# pca10156_sheet7_connectors.net
KiCad netlist of a schematic drawn in Altium Designer
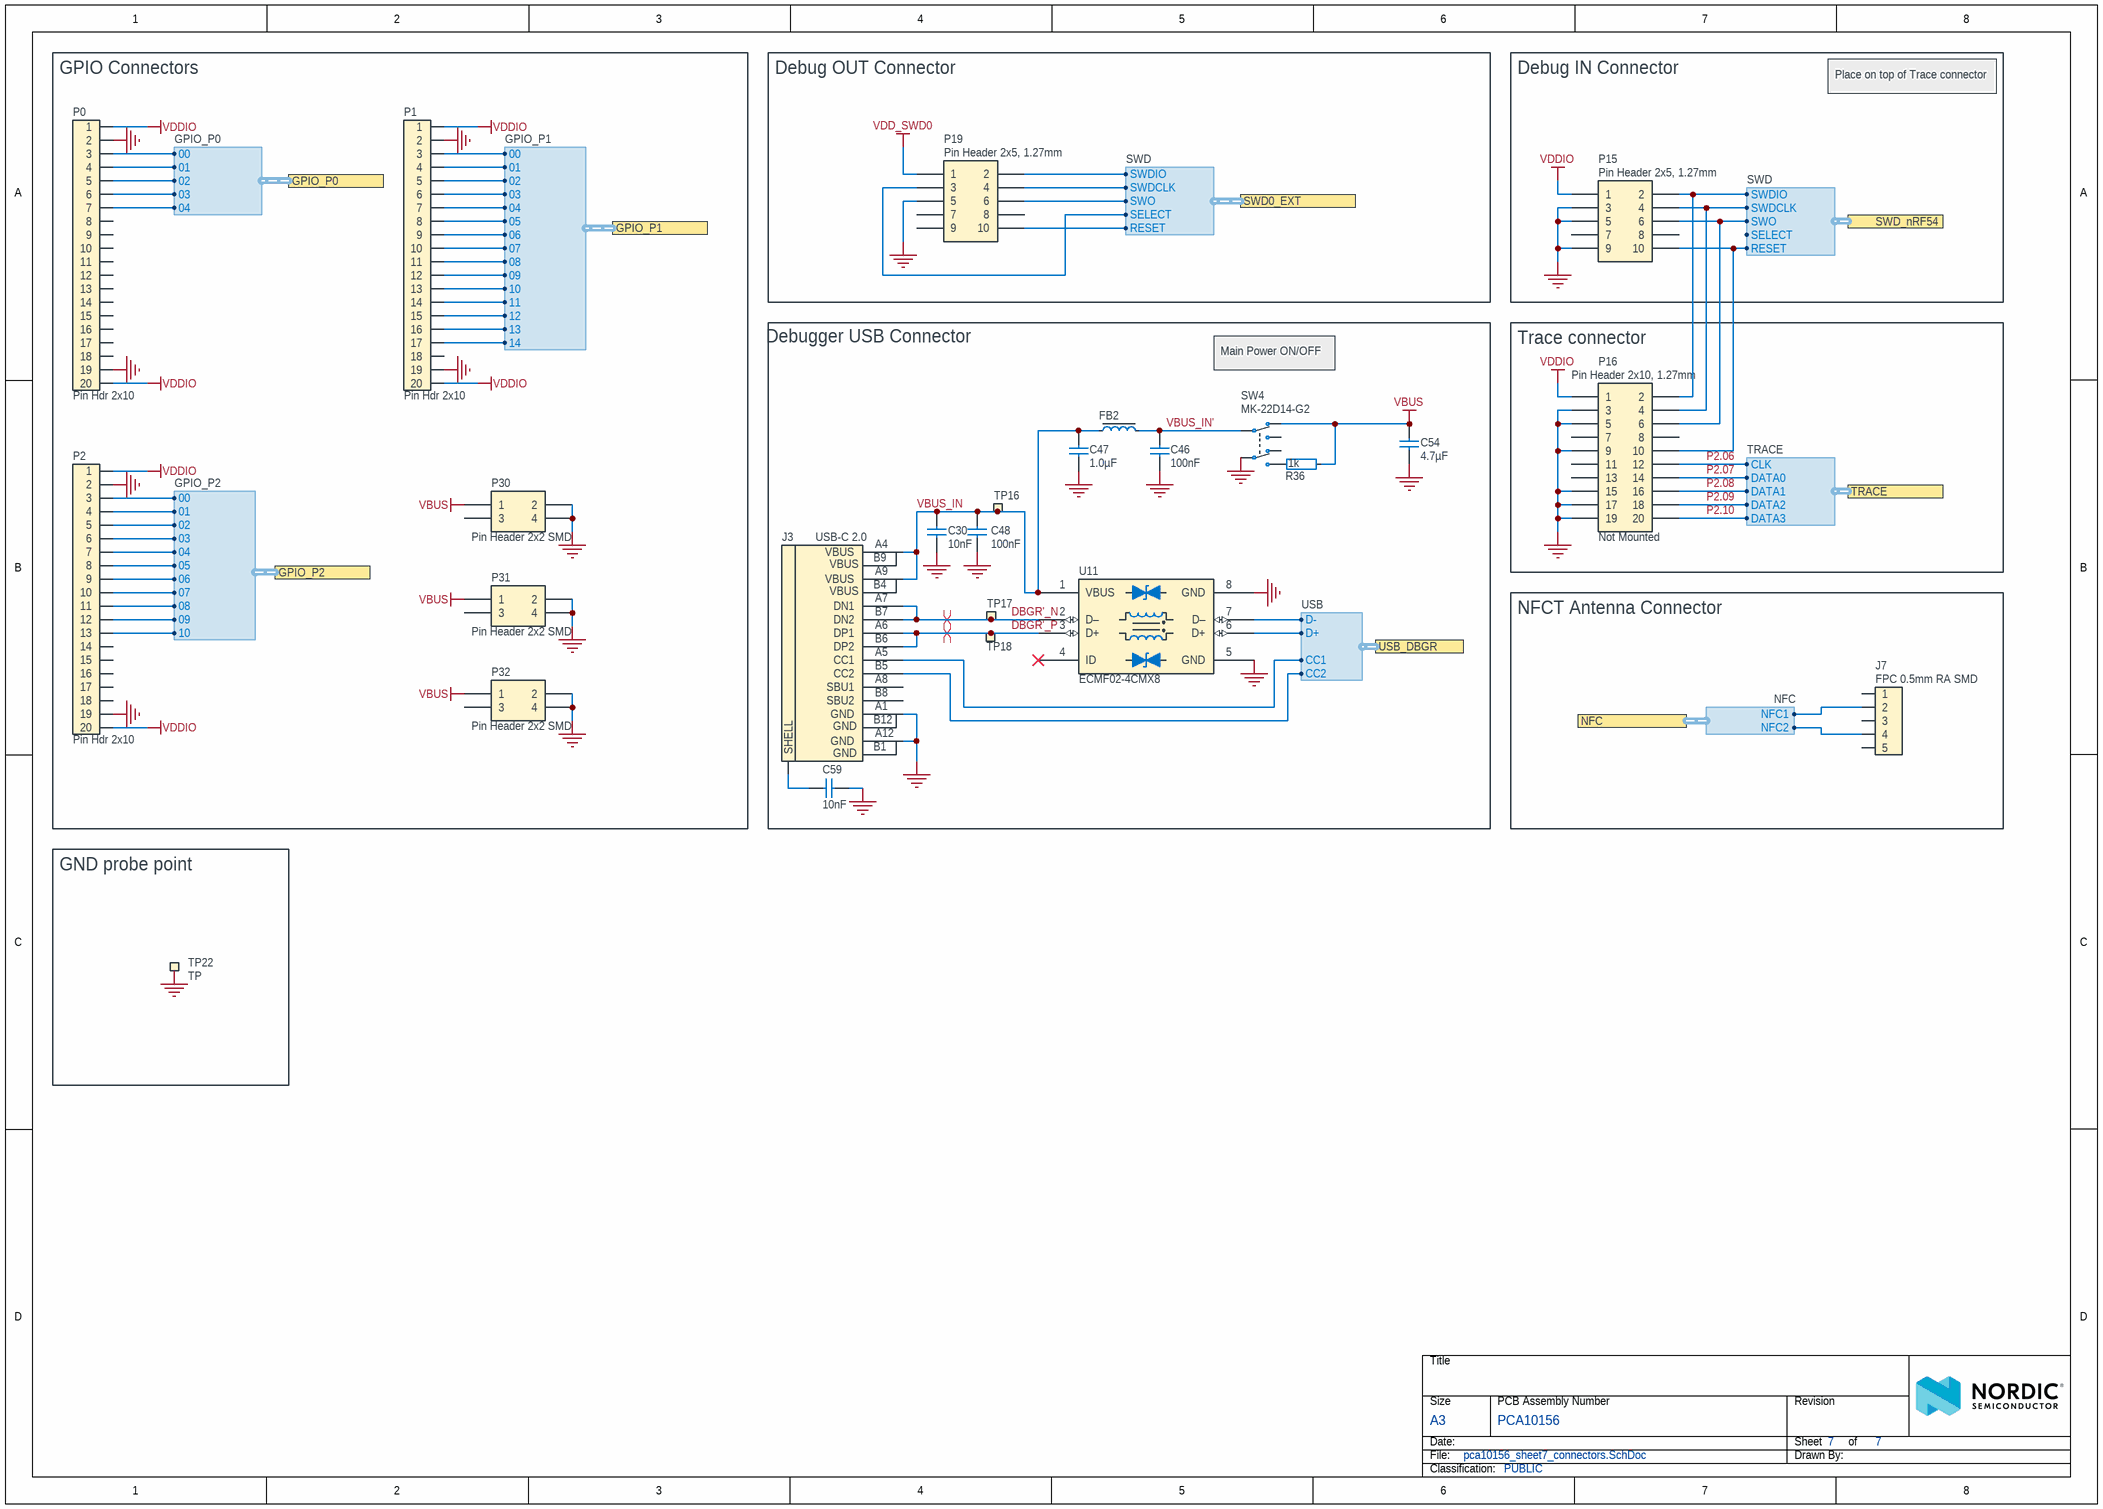
[diagram p0: pca10156_sheet7_connectors.SchDoc]

(export (version "E")
  (design (tool "Eeschema 10.0.6"))
  (components
    (comp (ref "C30")
      (value "10nF")
      (footprint "CAPC0603X03L_C")
      (description "Capacitor, X7R, ±10%")
      (fields
        (field (name "PART NUMBER") "C0201-10n")
        (field (name "MANUFACTURER") "N.A.")
        (field (name "AUTHOR") "rsk")
      )
      (libsource (lib "AltiumLib") (part "CAP"))
    )
    (comp (ref "C46")
      (value "100nF")
      (footprint "CAPC0603X03L_C")
      (description "Capacitor, X5R, ±10%")
      (fields
        (field (name "PART NUMBER") "C0201-100n")
        (field (name "MANUFACTURER") "N.A.")
        (field (name "AUTHOR") "rsk")
      )
      (libsource (lib "AltiumLib") (part "CAP"))
    )
    (comp (ref "C47")
      (value "1.0µF")
      (footprint "CAPC1005X04L")
      (description "Capacitor, Ceramic, X5R, ±10%, 16V")
      (fields
        (field (name "PART NUMBER") "C0402-1µ0-16V-X5R")
        (field (name "MANUFACTURER") "Murata")
        (field (name "AUTHOR") "rsk")
      )
      (libsource (lib "AltiumLib") (part "CAP"))
    )
    (comp (ref "C48")
      (value "100nF")
      (footprint "CAPC0603X03L_C")
      (description "Capacitor, X5R, ±10%")
      (fields
        (field (name "PART NUMBER") "C0201-100n")
        (field (name "MANUFACTURER") "N.A.")
        (field (name "AUTHOR") "rsk")
      )
      (libsource (lib "AltiumLib") (part "CAP"))
    )
    (comp (ref "C54")
      (value "4.7µF")
      (footprint "CAPC1608X06L")
      (description "Capacitor, X7S, ±10%, 10V")
      (fields
        (field (name "PART NUMBER") "C0603-4µ7-10V-X7S")
        (field (name "MANUFACTURER") "N.A.")
        (field (name "AUTHOR") "rsk")
      )
      (libsource (lib "AltiumLib") (part "CAP"))
    )
    (comp (ref "C59")
      (value "10nF")
      (footprint "CAPC1608X06L")
      (description "Capacitor, X7R, ±10%, 100V")
      (fields
        (field (name "PART NUMBER") "C0603-10n-100V-X7R")
        (field (name "MANUFACTURER") "Murata")
        (field (name "AUTHOR") "rsk")
      )
      (libsource (lib "") (part "CAP_1"))
    )
    (comp (ref "FB2")
      (value "120R/0.55A")
      (footprint "INDC1005X04L")
      (description "Ferrite Bead, 120 Ohm @ 100MHz, 500mA, 250 mOhm Max")
      (fields
        (field (name "PART NUMBER") "FB0402-120R@100M-500mA")
        (field (name "MANUFACTURER") "Murata")
        (field (name "AUTHOR") "rsk")
      )
      (libsource (lib "AltiumLib") (part "IND_F"))
    )
    (comp (ref "J3")
      (value "USB-C 2.0")
      (footprint "SD-80259-001")
      (description "USB-C Receptacle, 16 Pin, USB 2.0")
      (fields
        (field (name "PART NUMBER") "SD-80259-1021")
        (field (name "MANUFACTURER") "Bellweather Electronic Corp.")
        (field (name "AUTHOR") "getr")
      )
      (libsource (lib "AltiumLib") (part "USB4110"))
    )
    (comp (ref "J7")
      (value "FPC 0.5mm RA SMD")
      (footprint "FPC_05P-0.5mm-RA-SMD")
      (description "0.5mm FPC, 5P,Right Angle SMT,Double Contact,H=1.2mm,White, Tin plated")
      (fields
        (field (name "PART NUMBER") "FPC_05P-0.5mm-RA-SMD")
        (field (name "MANUFACTURER") "WCON")
        (field (name "AUTHOR") "rsk")
      )
      (libsource (lib "AltiumLib") (part "CONN-5"))
    )
    (comp (ref "P0")
      (value "Pin Hdr 2x10")
      (footprint "HDR_2x10-SMD")
      (description "Pin Header 2x10, 2.54mm (100mil) SMD")
      (fields
        (field (name "PART NUMBER") "Pin Header 2x10 SMD, 2.54mm")
        (field (name "MANUFACTURER") "WCON")
        (field (name "AUTHOR") "stl1")
      )
      (libsource (lib "AltiumLib") (part "CONN-20"))
    )
    (comp (ref "P1")
      (value "Pin Hdr 2x10")
      (footprint "HDR_2x10-SMD")
      (description "Pin Header 2x10, 2.54mm (100mil) SMD")
      (fields
        (field (name "PART NUMBER") "Pin Header 2x10 SMD, 2.54mm")
        (field (name "MANUFACTURER") "WCON")
        (field (name "AUTHOR") "stl1")
      )
      (libsource (lib "AltiumLib") (part "CONN-20"))
    )
    (comp (ref "P2")
      (value "Pin Hdr 2x10")
      (footprint "HDR_2x10-SMD")
      (description "Pin Header 2x10, 2.54mm (100mil) SMD")
      (fields
        (field (name "PART NUMBER") "Pin Header 2x10 SMD, 2.54mm")
        (field (name "MANUFACTURER") "WCON")
        (field (name "AUTHOR") "stl1")
      )
      (libsource (lib "AltiumLib") (part "CONN-20"))
    )
    (comp (ref "P15")
      (value "Pin Header 2x5, 1.27mm")
      (footprint "HDR_2x5-SMD-1.27mm-K")
      (description "Pin Header 2x5, 1.27mm (50mil), SMD, Keying Shroud")
      (fields
        (field (name "PART NUMBER") "Pin Header 2x5 SMD, 1.27mm, KS")
        (field (name "MANUFACTURER") "WCON")
        (field (name "AUTHOR") "rsk")
      )
      (libsource (lib "AltiumLib") (part "CONN-2x5"))
    )
    (comp (ref "P16")
      (value "Pin Header 2x10, 1.27mm")
      (footprint "HDR_2x10-SMD-1.27mm-NC")
      (description "Pin Header 2x10, 1.27mm (50mil), SMD, Keying Shroud")
      (fields
        (field (name "PART NUMBER") "Pin Header 2x10 SMD, 1.27mm, KS, N.C.")
        (field (name "MANUFACTURER") "WCON")
        (field (name "ASSEMBLY") "Not Mounted")
        (field (name "AUTHOR") "rsk")
      )
      (libsource (lib "AltiumLib") (part "CONN-2x10"))
    )
    (comp (ref "P19")
      (value "Pin Header 2x5, 1.27mm")
      (footprint "HDR_2x5-SMD-1.27mm-K")
      (description "Pin Header 2x5, 1.27mm (50mil), SMD, Keying Shroud")
      (fields
        (field (name "PART NUMBER") "Pin Header 2x5 SMD, 1.27mm, KS")
        (field (name "MANUFACTURER") "WCON")
        (field (name "AUTHOR") "rsk")
      )
      (libsource (lib "AltiumLib") (part "CONN-2x5"))
    )
    (comp (ref "P30")
      (value "Pin Header 2x2 SMD")
      (footprint "HDR_2x2-SMD")
      (description "Pin Header 2x2, SMD, 2.54mm (100mil)")
      (fields
        (field (name "MANUFACTURER") "WCON")
        (field (name "MANUFACTURER PART NUMBER") "1125-1202S0M116CR03")
        (field (name "AUTHOR") "stl1")
      )
      (libsource (lib "AltiumLib") (part "CONN-2x2"))
    )
    (comp (ref "P31")
      (value "Pin Header 2x2 SMD")
      (footprint "HDR_2x2-SMD")
      (description "Pin Header 2x2, SMD, 2.54mm (100mil)")
      (fields
        (field (name "MANUFACTURER") "WCON")
        (field (name "MANUFACTURER PART NUMBER") "1125-1202S0M116CR03")
        (field (name "AUTHOR") "stl1")
      )
      (libsource (lib "AltiumLib") (part "CONN-2x2"))
    )
    (comp (ref "P32")
      (value "Pin Header 2x2 SMD")
      (footprint "HDR_2x2-SMD")
      (description "Pin Header 2x2, SMD, 2.54mm (100mil)")
      (fields
        (field (name "MANUFACTURER") "WCON")
        (field (name "MANUFACTURER PART NUMBER") "1125-1202S0M116CR03")
        (field (name "AUTHOR") "stl1")
      )
      (libsource (lib "AltiumLib") (part "CONN-2x2"))
    )
    (comp (ref "R36")
      (value "1k")
      (footprint "RESC0603X03L_C")
      (description "Resistor, ±1%, 0.05W")
      (fields
        (field (name "PART NUMBER") "R0201-1k0")
        (field (name "MANUFACTURER") "N.A.")
        (field (name "AUTHOR") "rsk")
      )
      (libsource (lib "AltiumLib") (part "RES"))
    )
    (comp (ref "SW4")
      (value "MK-22D14-G2")
      (footprint "MK-22D14-G2")
      (description "Slide Switch DPDT")
      (fields (field (name "MANUFACTURER") "HUA-JIE CORP.") (field (name "AUTHOR") "rsk"))
      (libsource (lib "AltiumLib") (part "SW-DPDT"))
    )
    (comp (ref "TP16")
      (value "Ø1.5mm,SMD")
      (footprint "TP_SMD_D1.5mm")
      (description "1.5mm circular SMD testpad")
      (fields
        (field (name "PART NUMBER") "TP_SMD_Ø1.5MM")
        (field (name "MANUFACTURER") "Nordic Semiconductor")
        (field (name "AUTHOR") "rsk")
      )
      (libsource (lib "AltiumLib") (part "TESTPAD"))
    )
    (comp (ref "TP17")
      (value "Ø1.5mm,SMD")
      (footprint "TP_SMD_D1.5mm")
      (description "1.5mm circular SMD testpad")
      (fields
        (field (name "PART NUMBER") "TP_SMD_Ø1.5MM")
        (field (name "MANUFACTURER") "Nordic Semiconductor")
        (field (name "AUTHOR") "rsk")
      )
      (libsource (lib "AltiumLib") (part "TESTPAD"))
    )
    (comp (ref "TP18")
      (value "Ø1.5mm,SMD")
      (footprint "TP_SMD_D1.5mm")
      (description "1.5mm circular SMD testpad")
      (fields
        (field (name "PART NUMBER") "TP_SMD_Ø1.5MM")
        (field (name "MANUFACTURER") "Nordic Semiconductor")
        (field (name "AUTHOR") "rsk")
      )
      (libsource (lib "") (part "TESTPAD_1"))
    )
    (comp (ref "TP22")
      (value "TP")
      (footprint "S1751")
      (description "PC TEST POINT TIN SMD L")
      (fields
        (field (name "PART NUMBER") "TP - S1751-46R")
        (field (name "MANUFACTURER") "Harwin")
        (field (name "AUTHOR") "rsk")
      )
      (libsource (lib "AltiumLib") (part "TESTPOINT_BOM"))
    )
    (comp (ref "U11")
      (value "ECMF02-4CMX8")
      (footprint "UFDFN50P120X250X55-8N")
      (description "2 Line Common mode filter with ESD protection for USB 2.0 interface")
      (fields (field (name "MANUFACTURER") "STMicroelectronics") (field (name "AUTHOR") "eisk"))
      (libsource (lib "AltiumLib") (part "ECMF02-4CMX8"))
    )
  )
  (nets
    (net (code "8") (name "/11") (class "Default")
      (node (ref "P1") (pin "14") (pinfunction "14_14") (pintype "passive"))
    )
    (net (code "9") (name "/12") (class "Default")
      (node (ref "P1") (pin "15") (pinfunction "15_15") (pintype "passive"))
    )
    (net (code "10") (name "/13") (class "Default")
      (node (ref "P1") (pin "16") (pinfunction "16_16") (pintype "passive"))
    )
    (net (code "11") (name "/14") (class "Default")
      (node (ref "P1") (pin "17") (pinfunction "17_17") (pintype "passive"))
    )
    (net (code "12") (name "/CC1") (class "Default")
      (node (ref "J3") (pin "A5") (pinfunction "CC1_A5") (pintype "passive"))
    )
    (net (code "13") (name "/CC2") (class "Default")
      (node (ref "J3") (pin "B5") (pinfunction "CC2_B5") (pintype "passive"))
    )
    (net (code "14") (name "/D+") (class "Default")
      (node (ref "U11") (pin "6") (pinfunction "D+_6") (pintype "bidirectional"))
    )
    (net (code "15") (name "/D-") (class "Default")
      (node (ref "U11") (pin "7") (pinfunction "D–_7") (pintype "bidirectional"))
    )
    (net (code "16") (name "/DBGR'_N") (class "Default")
      (node (ref "J3") (pin "A7") (pinfunction "DN1_A7") (pintype "passive"))
      (node (ref "J3") (pin "B7") (pinfunction "DN2_B7") (pintype "passive"))
      (node (ref "TP17") (pin "1") (pinfunction "1_1") (pintype "passive"))
      (node (ref "U11") (pin "2") (pinfunction "D–_2") (pintype "bidirectional"))
    )
    (net (code "17") (name "/DBGR'_P") (class "Default")
      (node (ref "J3") (pin "A6") (pinfunction "DP1_A6") (pintype "passive"))
      (node (ref "J3") (pin "B6") (pinfunction "DP2_B6") (pintype "passive"))
      (node (ref "TP18") (pin "1") (pinfunction "1_1") (pintype "passive"))
      (node (ref "U11") (pin "3") (pinfunction "D+_3") (pintype "bidirectional"))
    )
    (net (code "18") (name "/NFC1") (class "Default")
      (node (ref "J7") (pin "2") (pinfunction "2_2") (pintype "passive"))
    )
    (net (code "19") (name "/NFC2") (class "Default")
      (node (ref "J7") (pin "4") (pinfunction "4_4") (pintype "passive"))
    )
    (net (code "20") (name "/P2.06") (class "Default")
      (node (ref "P16") (pin "12") (pinfunction "12_12") (pintype "passive"))
    )
    (net (code "21") (name "/P2.07") (class "Default")
      (node (ref "P16") (pin "14") (pinfunction "14_14") (pintype "passive"))
    )
    (net (code "22") (name "/P2.08") (class "Default")
      (node (ref "P16") (pin "16") (pinfunction "16_16") (pintype "passive"))
    )
    (net (code "23") (name "/P2.09") (class "Default")
      (node (ref "P16") (pin "18") (pinfunction "18_18") (pintype "passive"))
    )
    (net (code "24") (name "/P2.10") (class "Default")
      (node (ref "P16") (pin "20") (pinfunction "20_20") (pintype "passive"))
    )
    (net (code "25") (name "/VBUS_IN") (class "Default")
      (node (ref "C30") (pin "1") (pinfunction "1_1") (pintype "passive"))
      (node (ref "C47") (pin "2") (pinfunction "2_2") (pintype "passive"))
      (node (ref "C48") (pin "2") (pinfunction "2_2") (pintype "passive"))
      (node (ref "FB2") (pin "1") (pinfunction "1_1") (pintype "passive"))
      (node (ref "J3") (pin "A4") (pinfunction "VBUS_A4") (pintype "power_in"))
      (node (ref "J3") (pin "A9") (pinfunction "VBUS_A9") (pintype "power_in"))
      (node (ref "TP16") (pin "1") (pinfunction "1_1") (pintype "passive"))
      (node (ref "U11") (pin "1") (pinfunction "VBUS_1") (pintype "power_in"))
    )
    (net (code "26") (name "/VBUS_IN'") (class "Default")
      (node (ref "C46") (pin "2") (pinfunction "2_2") (pintype "passive"))
      (node (ref "FB2") (pin "2") (pinfunction "2_2") (pintype "passive"))
      (node (ref "SW4") (pin "2") (pinfunction "COM-1_2") (pintype "passive"))
    )
    (net (code "34") (name "GND") (class "Default")
      (node (ref "C30") (pin "2") (pinfunction "2_2") (pintype "passive"))
      (node (ref "C46") (pin "1") (pinfunction "1_1") (pintype "passive"))
      (node (ref "C47") (pin "1") (pinfunction "1_1") (pintype "passive"))
      (node (ref "C48") (pin "1") (pinfunction "1_1") (pintype "passive"))
      (node (ref "C54") (pin "2") (pinfunction "2_2") (pintype "passive"))
      (node (ref "C59") (pin "2") (pinfunction "2_2") (pintype "passive"))
      (node (ref "J3") (pin "A1") (pinfunction "GND_A1") (pintype "power_in"))
      (node (ref "J3") (pin "A12") (pinfunction "GND_A12") (pintype "power_in"))
      (node (ref "P0") (pin "19") (pinfunction "19_19") (pintype "passive"))
      (node (ref "P0") (pin "2") (pinfunction "2_2") (pintype "passive"))
      (node (ref "P1") (pin "19") (pinfunction "19_19") (pintype "passive"))
      (node (ref "P1") (pin "2") (pinfunction "2_2") (pintype "passive"))
      (node (ref "P15") (pin "3") (pinfunction "3_3") (pintype "passive"))
      (node (ref "P15") (pin "5") (pinfunction "5_5") (pintype "passive"))
      (node (ref "P15") (pin "9") (pinfunction "9_9") (pintype "passive"))
      (node (ref "P16") (pin "15") (pinfunction "15_15") (pintype "passive"))
      (node (ref "P16") (pin "17") (pinfunction "17_17") (pintype "passive"))
      (node (ref "P16") (pin "19") (pinfunction "19_19") (pintype "passive"))
      (node (ref "P16") (pin "3") (pinfunction "3_3") (pintype "passive"))
      (node (ref "P16") (pin "5") (pinfunction "5_5") (pintype "passive"))
      (node (ref "P16") (pin "9") (pinfunction "9_9") (pintype "passive"))
      (node (ref "P19") (pin "5") (pinfunction "5_5") (pintype "passive"))
      (node (ref "P2") (pin "19") (pinfunction "19_19") (pintype "passive"))
      (node (ref "P2") (pin "2") (pinfunction "2_2") (pintype "passive"))
      (node (ref "P30") (pin "2") (pinfunction "2_2") (pintype "passive"))
      (node (ref "P30") (pin "4") (pinfunction "4_4") (pintype "passive"))
      (node (ref "P31") (pin "2") (pinfunction "2_2") (pintype "passive"))
      (node (ref "P31") (pin "4") (pinfunction "4_4") (pintype "passive"))
      (node (ref "P32") (pin "2") (pinfunction "2_2") (pintype "passive"))
      (node (ref "P32") (pin "4") (pinfunction "4_4") (pintype "passive"))
      (node (ref "SW4") (pin "5") (pinfunction "COM-2_5") (pintype "passive"))
      (node (ref "TP22") (pin "1") (pinfunction "1_1") (pintype "passive"))
      (node (ref "U11") (pin "5") (pinfunction "GND_5") (pintype "power_in"))
      (node (ref "U11") (pin "8") (pinfunction "GND_8") (pintype "power_in"))
    )
    (net (code "35") (name "Net-(J3-SHELL)") (class "Default")
      (node (ref "C59") (pin "1") (pinfunction "1_1") (pintype "passive"))
      (node (ref "J3") (pin "SHLD") (pinfunction "SHELL_SHLD") (pintype "power_in"))
    )
    (net (code "36") (name "Net-(P15-Pad2)") (class "Default")
      (node (ref "P15") (pin "2") (pinfunction "2_2") (pintype "passive"))
      (node (ref "P16") (pin "2") (pinfunction "2_2") (pintype "passive"))
    )
    (net (code "37") (name "Net-(P15-Pad4)") (class "Default")
      (node (ref "P15") (pin "4") (pinfunction "4_4") (pintype "passive"))
      (node (ref "P16") (pin "4") (pinfunction "4_4") (pintype "passive"))
    )
    (net (code "38") (name "Net-(P15-Pad6)") (class "Default")
      (node (ref "P15") (pin "6") (pinfunction "6_6") (pintype "passive"))
      (node (ref "P16") (pin "6") (pinfunction "6_6") (pintype "passive"))
    )
    (net (code "39") (name "Net-(P15-Pad10)") (class "Default")
      (node (ref "P15") (pin "10") (pinfunction "10_10") (pintype "passive"))
      (node (ref "P16") (pin "10") (pinfunction "10_10") (pintype "passive"))
    )
    (net (code "40") (name "Net-(SW4-N.O-2)") (class "Default")
      (node (ref "R36") (pin "1") (pinfunction "1_1") (pintype "passive"))
      (node (ref "SW4") (pin "4") (pinfunction "N.O-2_4") (pintype "passive"))
    )
    (net (code "41") (name "VBUS") (class "Default")
      (node (ref "C54") (pin "1") (pinfunction "1_1") (pintype "passive"))
      (node (ref "P30") (pin "1") (pinfunction "1_1") (pintype "passive"))
      (node (ref "P31") (pin "1") (pinfunction "1_1") (pintype "passive"))
      (node (ref "P32") (pin "1") (pinfunction "1_1") (pintype "passive"))
      (node (ref "R36") (pin "2") (pinfunction "2_2") (pintype "passive"))
      (node (ref "SW4") (pin "3") (pinfunction "N.C-1_3") (pintype "passive"))
    )
    (net (code "42") (name "VDDIO") (class "Default")
      (node (ref "P0") (pin "1") (pinfunction "1_1") (pintype "passive"))
      (node (ref "P0") (pin "20") (pinfunction "20_20") (pintype "passive"))
      (node (ref "P1") (pin "1") (pinfunction "1_1") (pintype "passive"))
      (node (ref "P1") (pin "20") (pinfunction "20_20") (pintype "passive"))
      (node (ref "P15") (pin "1") (pinfunction "1_1") (pintype "passive"))
      (node (ref "P16") (pin "1") (pinfunction "1_1") (pintype "passive"))
      (node (ref "P2") (pin "1") (pinfunction "1_1") (pintype "passive"))
      (node (ref "P2") (pin "20") (pinfunction "20_20") (pintype "passive"))
    )
    (net (code "43") (name "VDD_SWD0") (class "Default")
      (node (ref "P19") (pin "1") (pinfunction "1_1") (pintype "passive"))
    )
    (net (code "44") (name "unconnected-(J3-SBU1-PadA8)") (class "Default")
      (node (ref "J3") (pin "A8") (pinfunction "SBU1_A8") (pintype "passive"))
    )
    (net (code "45") (name "unconnected-(J3-SBU2-PadB8)") (class "Default")
      (node (ref "J3") (pin "B8") (pinfunction "SBU2_B8") (pintype "passive"))
    )
    (net (code "46") (name "unconnected-(J7-Pad1)") (class "Default")
      (node (ref "J7") (pin "1") (pinfunction "1_1") (pintype "passive"))
    )
    (net (code "47") (name "unconnected-(J7-Pad3)") (class "Default")
      (node (ref "J7") (pin "3") (pinfunction "3_3") (pintype "passive"))
    )
    (net (code "48") (name "unconnected-(J7-Pad5)") (class "Default")
      (node (ref "J7") (pin "5") (pinfunction "5_5") (pintype "passive"))
    )
    (net (code "49") (name "unconnected-(P0-Pad3)") (class "Default")
      (node (ref "P0") (pin "3") (pinfunction "3_3") (pintype "passive"))
    )
    (net (code "50") (name "unconnected-(P0-Pad4)") (class "Default")
      (node (ref "P0") (pin "4") (pinfunction "4_4") (pintype "passive"))
    )
    (net (code "51") (name "unconnected-(P0-Pad5)") (class "Default")
      (node (ref "P0") (pin "5") (pinfunction "5_5") (pintype "passive"))
    )
    (net (code "52") (name "unconnected-(P0-Pad6)") (class "Default")
      (node (ref "P0") (pin "6") (pinfunction "6_6") (pintype "passive"))
    )
    (net (code "53") (name "unconnected-(P0-Pad7)") (class "Default")
      (node (ref "P0") (pin "7") (pinfunction "7_7") (pintype "passive"))
    )
    (net (code "54") (name "unconnected-(P0-Pad8)") (class "Default")
      (node (ref "P0") (pin "8") (pinfunction "8_8") (pintype "passive"))
    )
    (net (code "55") (name "unconnected-(P0-Pad9)") (class "Default")
      (node (ref "P0") (pin "9") (pinfunction "9_9") (pintype "passive"))
    )
    (net (code "56") (name "unconnected-(P0-Pad10)") (class "Default")
      (node (ref "P0") (pin "10") (pinfunction "10_10") (pintype "passive"))
    )
    (net (code "57") (name "unconnected-(P0-Pad11)") (class "Default")
      (node (ref "P0") (pin "11") (pinfunction "11_11") (pintype "passive"))
    )
    (net (code "58") (name "unconnected-(P0-Pad12)") (class "Default")
      (node (ref "P0") (pin "12") (pinfunction "12_12") (pintype "passive"))
    )
    (net (code "59") (name "unconnected-(P0-Pad13)") (class "Default")
      (node (ref "P0") (pin "13") (pinfunction "13_13") (pintype "passive"))
    )
    (net (code "60") (name "unconnected-(P0-Pad14)") (class "Default")
      (node (ref "P0") (pin "14") (pinfunction "14_14") (pintype "passive"))
    )
    (net (code "61") (name "unconnected-(P0-Pad15)") (class "Default")
      (node (ref "P0") (pin "15") (pinfunction "15_15") (pintype "passive"))
    )
    (net (code "62") (name "unconnected-(P0-Pad16)") (class "Default")
      (node (ref "P0") (pin "16") (pinfunction "16_16") (pintype "passive"))
    )
    (net (code "63") (name "unconnected-(P0-Pad17)") (class "Default")
      (node (ref "P0") (pin "17") (pinfunction "17_17") (pintype "passive"))
    )
    (net (code "64") (name "unconnected-(P0-Pad18)") (class "Default")
      (node (ref "P0") (pin "18") (pinfunction "18_18") (pintype "passive"))
    )
    (net (code "65") (name "unconnected-(P1-Pad3)") (class "Default")
      (node (ref "P1") (pin "3") (pinfunction "3_3") (pintype "passive"))
    )
    (net (code "66") (name "unconnected-(P1-Pad4)") (class "Default")
      (node (ref "P1") (pin "4") (pinfunction "4_4") (pintype "passive"))
    )
    (net (code "67") (name "unconnected-(P1-Pad5)") (class "Default")
      (node (ref "P1") (pin "5") (pinfunction "5_5") (pintype "passive"))
    )
    (net (code "68") (name "unconnected-(P1-Pad6)") (class "Default")
      (node (ref "P1") (pin "6") (pinfunction "6_6") (pintype "passive"))
    )
    (net (code "69") (name "unconnected-(P1-Pad7)") (class "Default")
      (node (ref "P1") (pin "7") (pinfunction "7_7") (pintype "passive"))
    )
    (net (code "70") (name "unconnected-(P1-Pad8)") (class "Default")
      (node (ref "P1") (pin "8") (pinfunction "8_8") (pintype "passive"))
    )
    (net (code "71") (name "unconnected-(P1-Pad9)") (class "Default")
      (node (ref "P1") (pin "9") (pinfunction "9_9") (pintype "passive"))
    )
    (net (code "72") (name "unconnected-(P1-Pad10)") (class "Default")
      (node (ref "P1") (pin "10") (pinfunction "10_10") (pintype "passive"))
    )
    (net (code "73") (name "unconnected-(P1-Pad11)") (class "Default")
      (node (ref "P1") (pin "11") (pinfunction "11_11") (pintype "passive"))
    )
    (net (code "74") (name "unconnected-(P1-Pad12)") (class "Default")
      (node (ref "P1") (pin "12") (pinfunction "12_12") (pintype "passive"))
    )
    (net (code "75") (name "unconnected-(P1-Pad13)") (class "Default")
      (node (ref "P1") (pin "13") (pinfunction "13_13") (pintype "passive"))
    )
    (net (code "76") (name "unconnected-(P1-Pad18)") (class "Default")
      (node (ref "P1") (pin "18") (pinfunction "18_18") (pintype "passive"))
    )
    (net (code "77") (name "unconnected-(P2-Pad3)") (class "Default")
      (node (ref "P2") (pin "3") (pinfunction "3_3") (pintype "passive"))
    )
    (net (code "78") (name "unconnected-(P2-Pad4)") (class "Default")
      (node (ref "P2") (pin "4") (pinfunction "4_4") (pintype "passive"))
    )
    (net (code "79") (name "unconnected-(P2-Pad5)") (class "Default")
      (node (ref "P2") (pin "5") (pinfunction "5_5") (pintype "passive"))
    )
    (net (code "80") (name "unconnected-(P2-Pad6)") (class "Default")
      (node (ref "P2") (pin "6") (pinfunction "6_6") (pintype "passive"))
    )
    (net (code "81") (name "unconnected-(P2-Pad7)") (class "Default")
      (node (ref "P2") (pin "7") (pinfunction "7_7") (pintype "passive"))
    )
    (net (code "82") (name "unconnected-(P2-Pad8)") (class "Default")
      (node (ref "P2") (pin "8") (pinfunction "8_8") (pintype "passive"))
    )
    (net (code "83") (name "unconnected-(P2-Pad9)") (class "Default")
      (node (ref "P2") (pin "9") (pinfunction "9_9") (pintype "passive"))
    )
    (net (code "84") (name "unconnected-(P2-Pad10)") (class "Default")
      (node (ref "P2") (pin "10") (pinfunction "10_10") (pintype "passive"))
    )
    (net (code "85") (name "unconnected-(P2-Pad11)") (class "Default")
      (node (ref "P2") (pin "11") (pinfunction "11_11") (pintype "passive"))
    )
    (net (code "86") (name "unconnected-(P2-Pad12)") (class "Default")
      (node (ref "P2") (pin "12") (pinfunction "12_12") (pintype "passive"))
    )
    (net (code "87") (name "unconnected-(P2-Pad13)") (class "Default")
      (node (ref "P2") (pin "13") (pinfunction "13_13") (pintype "passive"))
    )
    (net (code "88") (name "unconnected-(P2-Pad14)") (class "Default")
      (node (ref "P2") (pin "14") (pinfunction "14_14") (pintype "passive"))
    )
    (net (code "89") (name "unconnected-(P2-Pad15)") (class "Default")
      (node (ref "P2") (pin "15") (pinfunction "15_15") (pintype "passive"))
    )
    (net (code "90") (name "unconnected-(P2-Pad16)") (class "Default")
      (node (ref "P2") (pin "16") (pinfunction "16_16") (pintype "passive"))
    )
    (net (code "91") (name "unconnected-(P2-Pad17)") (class "Default")
      (node (ref "P2") (pin "17") (pinfunction "17_17") (pintype "passive"))
    )
    (net (code "92") (name "unconnected-(P2-Pad18)") (class "Default")
      (node (ref "P2") (pin "18") (pinfunction "18_18") (pintype "passive"))
    )
    (net (code "93") (name "unconnected-(P15-Pad7)") (class "Default")
      (node (ref "P15") (pin "7") (pinfunction "7_7") (pintype "passive"))
    )
    (net (code "94") (name "unconnected-(P15-Pad8)") (class "Default")
      (node (ref "P15") (pin "8") (pinfunction "8_8") (pintype "passive"))
    )
    (net (code "95") (name "unconnected-(P16-Pad7)") (class "Default")
      (node (ref "P16") (pin "7") (pinfunction "7_7") (pintype "passive"))
    )
    (net (code "96") (name "unconnected-(P16-Pad8)") (class "Default")
      (node (ref "P16") (pin "8") (pinfunction "8_8") (pintype "passive"))
    )
    (net (code "97") (name "unconnected-(P16-Pad11)") (class "Default")
      (node (ref "P16") (pin "11") (pinfunction "11_11") (pintype "passive"))
    )
    (net (code "98") (name "unconnected-(P16-Pad13)") (class "Default")
      (node (ref "P16") (pin "13") (pinfunction "13_13") (pintype "passive"))
    )
    (net (code "99") (name "unconnected-(P19-Pad2)") (class "Default")
      (node (ref "P19") (pin "2") (pinfunction "2_2") (pintype "passive"))
    )
    (net (code "100") (name "unconnected-(P19-Pad3)") (class "Default")
      (node (ref "P19") (pin "3") (pinfunction "3_3") (pintype "passive"))
    )
    (net (code "101") (name "unconnected-(P19-Pad4)") (class "Default")
      (node (ref "P19") (pin "4") (pinfunction "4_4") (pintype "passive"))
    )
    (net (code "102") (name "unconnected-(P19-Pad6)") (class "Default")
      (node (ref "P19") (pin "6") (pinfunction "6_6") (pintype "passive"))
    )
    (net (code "103") (name "unconnected-(P19-Pad7)") (class "Default")
      (node (ref "P19") (pin "7") (pinfunction "7_7") (pintype "passive"))
    )
    (net (code "104") (name "unconnected-(P19-Pad8)") (class "Default")
      (node (ref "P19") (pin "8") (pinfunction "8_8") (pintype "passive"))
    )
    (net (code "105") (name "unconnected-(P19-Pad9)") (class "Default")
      (node (ref "P19") (pin "9") (pinfunction "9_9") (pintype "passive"))
    )
    (net (code "106") (name "unconnected-(P19-Pad10)") (class "Default")
      (node (ref "P19") (pin "10") (pinfunction "10_10") (pintype "passive"))
    )
    (net (code "107") (name "unconnected-(P30-Pad3)") (class "Default")
      (node (ref "P30") (pin "3") (pinfunction "3_3") (pintype "passive"))
    )
    (net (code "108") (name "unconnected-(P31-Pad3)") (class "Default")
      (node (ref "P31") (pin "3") (pinfunction "3_3") (pintype "passive"))
    )
    (net (code "109") (name "unconnected-(P32-Pad3)") (class "Default")
      (node (ref "P32") (pin "3") (pinfunction "3_3") (pintype "passive"))
    )
    (net (code "110") (name "unconnected-(SW4-N.C-2-Pad6)") (class "Default")
      (node (ref "SW4") (pin "6") (pinfunction "N.C-2_6") (pintype "passive"))
    )
    (net (code "111") (name "unconnected-(SW4-N.O-1-Pad1)") (class "Default")
      (node (ref "SW4") (pin "1") (pinfunction "N.O-1_1") (pintype "passive"))
    )
    (net (code "112") (name "unconnected-(U11-ID-Pad4)") (class "Default")
      (node (ref "U11") (pin "4") (pinfunction "ID_4") (pintype "passive+no_connect"))
    )
  )
)
